# PowerCell-v13.net
KiCad netlist of a schematic drawn in EAGLE
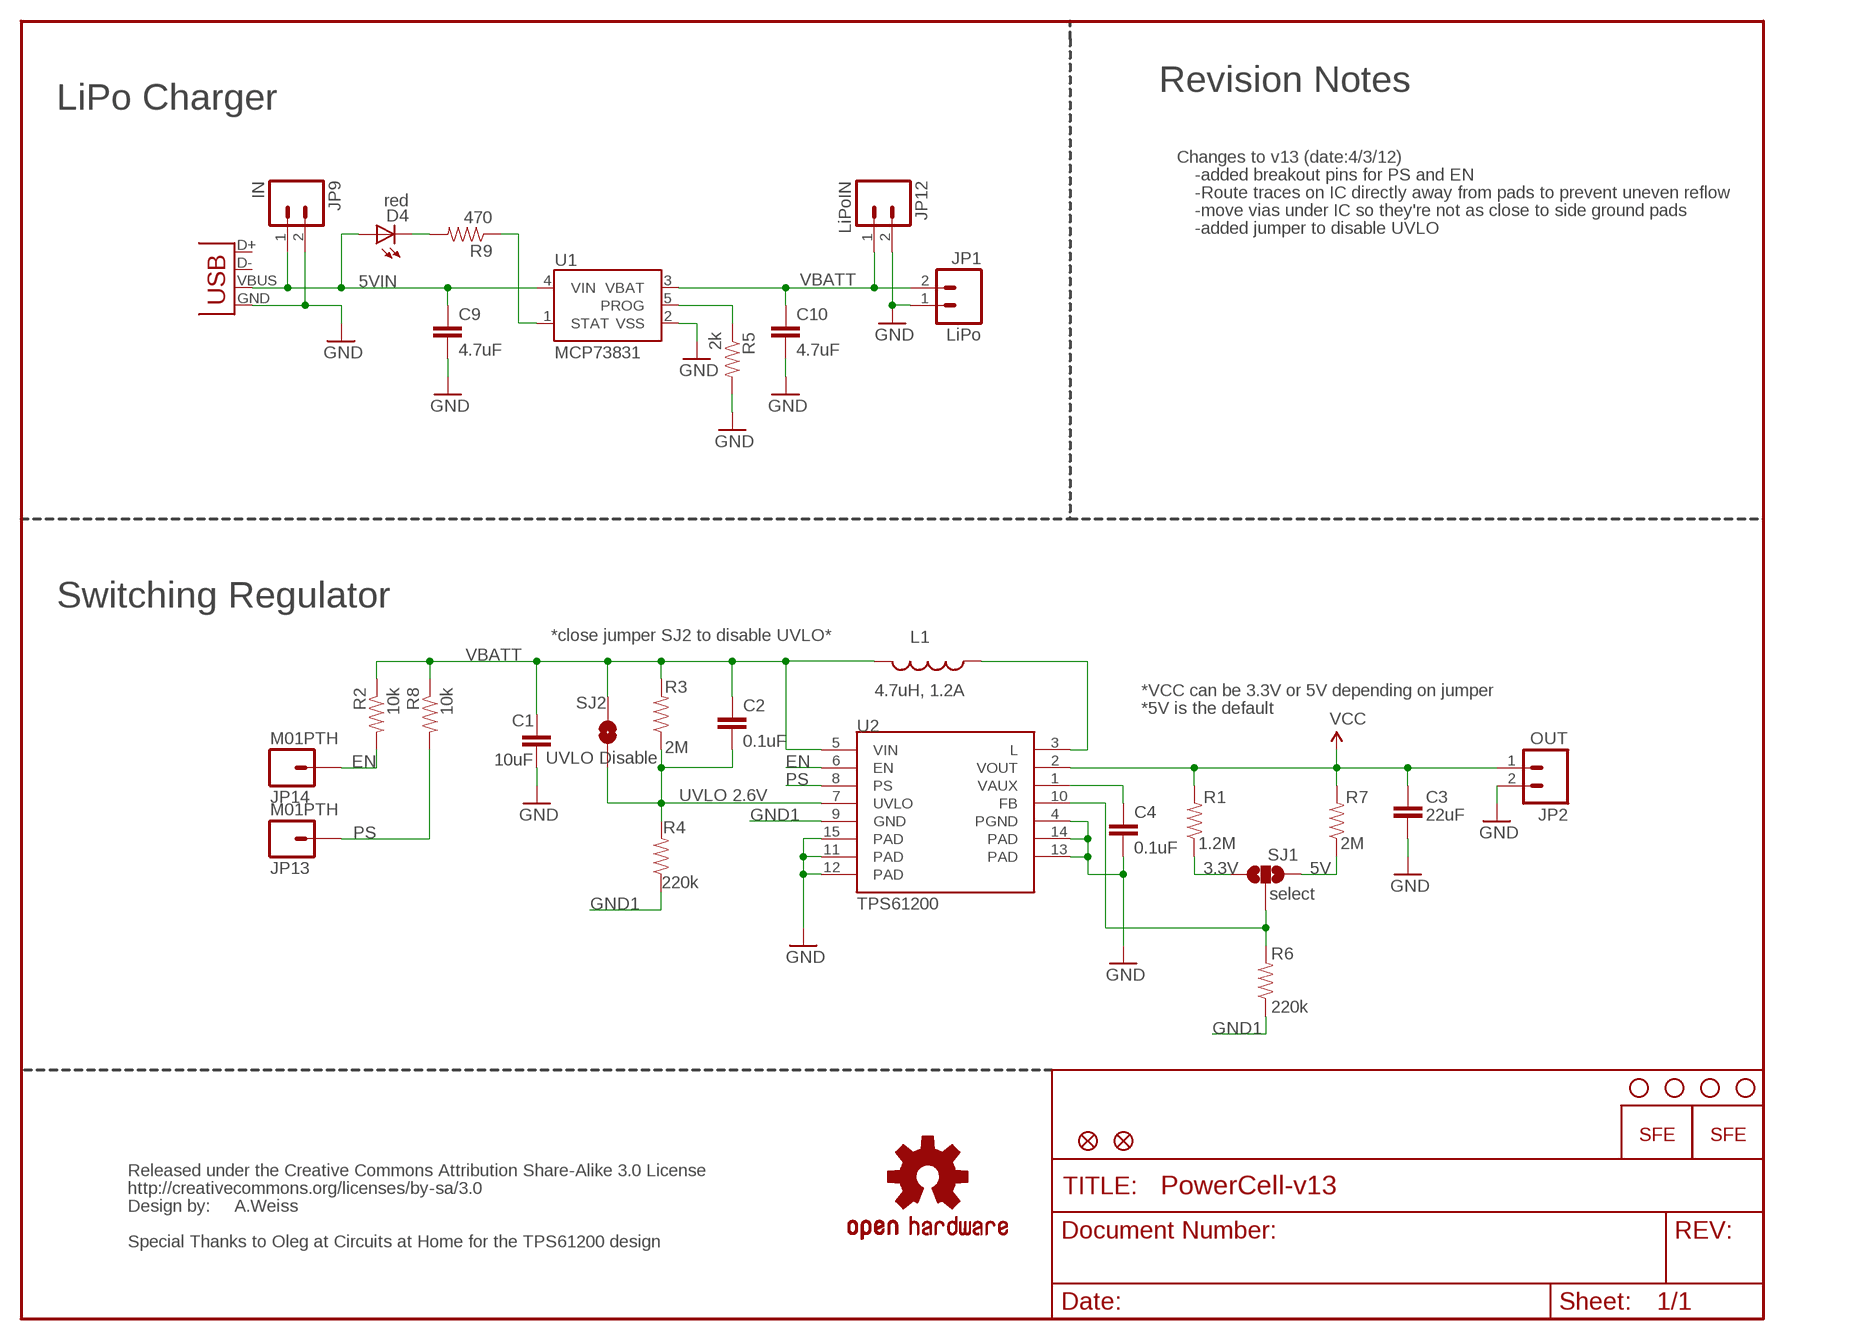
[diagram p0: schematic, sheet 1]

(export (version "E")
  (design (tool "Eeschema 10.0.6"))
  (components
    (comp (ref "C1")
      (value "10uF")
      (footprint "eagle-import:1206")
      (libsource (lib "eagle-import") (part "CAP1206"))
    )
    (comp (ref "C2")
      (value "0.1uF")
      (footprint "eagle-import:0402-CAP")
      (libsource (lib "eagle-import") (part "CAP0402-CAP"))
    )
    (comp (ref "C3")
      (value "22uF")
      (footprint "eagle-import:0805")
      (libsource (lib "eagle-import") (part "CAP0805"))
    )
    (comp (ref "C4")
      (value "0.1uF")
      (footprint "eagle-import:0402-CAP")
      (libsource (lib "eagle-import") (part "CAP0402-CAP"))
    )
    (comp (ref "C9")
      (value "4.7uF")
      (footprint "eagle-import:0402-CAP")
      (libsource (lib "eagle-import") (part "CAP0402-CAP"))
    )
    (comp (ref "C10")
      (value "4.7uF")
      (footprint "eagle-import:0402-CAP")
      (libsource (lib "eagle-import") (part "CAP0402-CAP"))
    )
    (comp (ref "D4")
      (value "red")
      (footprint "eagle-import:LED-0603")
      (libsource (lib "eagle-import") (part "LED0603"))
    )
    (comp (ref "JP1")
      (value "LiPo")
      (footprint "eagle-import:JST-2-SMD")
      (libsource (lib "eagle-import") (part "M02-JST-2MM-SMT"))
    )
    (comp (ref "JP2")
      (value "OUT")
      (footprint "eagle-import:1X02")
      (libsource (lib "eagle-import") (part "M02PTH"))
    )
    (comp (ref "JP3")
      (value "LOGO-SFENEW")
      (footprint "eagle-import:SFE-NEW-WEBLOGO")
      (libsource (lib "eagle-import") (part "LOGO-SFENEW"))
    )
    (comp (ref "JP4")
      (value "LOGO-SFESK")
      (footprint "eagle-import:SFE-LOGO-FLAME")
      (libsource (lib "eagle-import") (part "LOGO-SFESK"))
    )
    (comp (ref "JP5")
      (value "STAND-OFF")
      (footprint "eagle-import:STAND-OFF")
      (libsource (lib "eagle-import") (part "STAND-OFF"))
    )
    (comp (ref "JP6")
      (value "STAND-OFF")
      (footprint "eagle-import:STAND-OFF")
      (libsource (lib "eagle-import") (part "STAND-OFF"))
    )
    (comp (ref "JP7")
      (value "STAND-OFF")
      (footprint "eagle-import:STAND-OFF")
      (libsource (lib "eagle-import") (part "STAND-OFF"))
    )
    (comp (ref "JP8")
      (value "STAND-OFF")
      (footprint "eagle-import:STAND-OFF")
      (libsource (lib "eagle-import") (part "STAND-OFF"))
    )
    (comp (ref "JP9")
      (value "IN")
      (footprint "eagle-import:1X02")
      (libsource (lib "eagle-import") (part "M02PTH"))
    )
    (comp (ref "JP12")
      (value "LiPoIN")
      (footprint "eagle-import:1X02")
      (libsource (lib "eagle-import") (part "M02PTH"))
    )
    (comp (ref "JP13")
      (value "M01PTH")
      (footprint "eagle-import:1X01")
      (libsource (lib "eagle-import") (part "M01PTH"))
    )
    (comp (ref "JP14")
      (value "M01PTH")
      (footprint "eagle-import:1X01")
      (libsource (lib "eagle-import") (part "M01PTH"))
    )
    (comp (ref "JP15")
      (value "FIDUCIALUFIDUCIAL")
      (footprint "eagle-import:MICRO-FIDUCIAL")
      (libsource (lib "eagle-import") (part "FIDUCIALUFIDUCIAL"))
    )
    (comp (ref "JP16")
      (value "FIDUCIALUFIDUCIAL")
      (footprint "eagle-import:MICRO-FIDUCIAL")
      (libsource (lib "eagle-import") (part "FIDUCIALUFIDUCIAL"))
    )
    (comp (ref "L1")
      (value "4.7uH, 1.2A")
      (footprint "eagle-import:CDRH2D09")
      (libsource (lib "eagle-import") (part "INDUCTOR."))
    )
    (comp (ref "R1")
      (value "1.2M")
      (footprint "eagle-import:0402-RES")
      (libsource (lib "eagle-import") (part "RESISTOR0402-RES"))
    )
    (comp (ref "R2")
      (value "10k")
      (footprint "eagle-import:0402-RES")
      (libsource (lib "eagle-import") (part "RESISTOR0402-RES"))
    )
    (comp (ref "R3")
      (value "2M")
      (footprint "eagle-import:0402-RES")
      (libsource (lib "eagle-import") (part "RESISTOR0402-RES"))
    )
    (comp (ref "R4")
      (value "220k")
      (footprint "eagle-import:0402-RES")
      (libsource (lib "eagle-import") (part "RESISTOR0402-RES"))
    )
    (comp (ref "R5")
      (value "2k")
      (footprint "eagle-import:0402-RES")
      (libsource (lib "eagle-import") (part "RESISTOR0402-RES"))
    )
    (comp (ref "R6")
      (value "220k")
      (footprint "eagle-import:0402-RES")
      (libsource (lib "eagle-import") (part "RESISTOR0402-RES"))
    )
    (comp (ref "R7")
      (value "2M")
      (footprint "eagle-import:0402-RES")
      (libsource (lib "eagle-import") (part "RESISTOR0402-RES"))
    )
    (comp (ref "R8")
      (value "10k")
      (footprint "eagle-import:0402-RES")
      (libsource (lib "eagle-import") (part "RESISTOR0402-RES"))
    )
    (comp (ref "R9")
      (value "470")
      (footprint "eagle-import:0402-RES")
      (libsource (lib "eagle-import") (part "RESISTOR0402-RES"))
    )
    (comp (ref "SJ1")
      (value "select")
      (footprint "eagle-import:SJ_3_PASTE2&3")
      (libsource (lib "eagle-import") (part "SOLDERJUMPER_2WAYPASTE2&3"))
    )
    (comp (ref "SJ2")
      (value "UVLO Disable")
      (footprint "eagle-import:SJ_2S-NO")
      (libsource (lib "eagle-import") (part "SOLDERJUMPERNO"))
    )
    (comp (ref "U$1")
      (value "OSHW-LOGOS")
      (footprint "eagle-import:OSHW-LOGO-S")
      (libsource (lib "eagle-import") (part "OSHW-LOGOS"))
    )
    (comp (ref "U$2")
      (value "CREATIVE_COMMONS")
      (footprint "eagle-import:CREATIVE_COMMONS")
      (libsource (lib "eagle-import") (part "CREATIVE_COMMONS"))
    )
    (comp (ref "U1")
      (value "MCP73831")
      (footprint "eagle-import:SOT23-5")
      (libsource (lib "eagle-import") (part "MCP73831"))
    )
    (comp (ref "U2")
      (value "TPS61200")
      (footprint "eagle-import:QFN-10_PAD")
      (libsource (lib "eagle-import") (part "TPS61200"))
    )
    (comp (ref "X1")
      (value "USB-MICROB")
      (footprint "eagle-import:USB-MICROB")
      (libsource (lib "eagle-import") (part "USB-MICROB"))
    )
  )
  (nets
    (net (code "1") (name "/3.3V") (class "Default")
      (node (ref "R1") (pin "1") (pinfunction "1_1") (pintype "passive"))
      (node (ref "SJ1") (pin "1") (pinfunction "1_1") (pintype "passive"))
    )
    (net (code "2") (name "/5V") (class "Default")
      (node (ref "R7") (pin "1") (pinfunction "1_1") (pintype "passive"))
      (node (ref "SJ1") (pin "3") (pinfunction "3_3") (pintype "passive"))
    )
    (net (code "3") (name "/5VIN") (class "Default")
      (node (ref "C9") (pin "1") (pinfunction "1_1") (pintype "passive"))
      (node (ref "D4") (pin "A") (pinfunction "A_A") (pintype "passive"))
      (node (ref "JP9") (pin "1") (pinfunction "1_1") (pintype "passive"))
      (node (ref "U1") (pin "4") (pinfunction "VIN_4") (pintype "power_in"))
      (node (ref "X1") (pin "VBUS") (pinfunction "VBUS_VBUS") (pintype "bidirectional"))
    )
    (net (code "4") (name "/EN") (class "Default")
      (node (ref "JP14") (pin "1") (pinfunction "1_1") (pintype "passive"))
      (node (ref "R2") (pin "2") (pinfunction "2_2") (pintype "passive"))
      (node (ref "U2") (pin "6") (pinfunction "EN_6") (pintype "input"))
    )
    (net (code "5") (name "/GND1") (class "Default")
      (node (ref "R4") (pin "1") (pinfunction "1_1") (pintype "passive"))
      (node (ref "R6") (pin "1") (pinfunction "1_1") (pintype "passive"))
      (node (ref "U2") (pin "9") (pinfunction "GND_9") (pintype "power_in"))
    )
    (net (code "6") (name "/PS") (class "Default")
      (node (ref "JP13") (pin "1") (pinfunction "1_1") (pintype "passive"))
      (node (ref "R8") (pin "2") (pinfunction "2_2") (pintype "passive"))
      (node (ref "U2") (pin "8") (pinfunction "PS_8") (pintype "input"))
    )
    (net (code "7") (name "/VBATT") (class "Default")
      (node (ref "C1") (pin "1") (pinfunction "1_1") (pintype "passive"))
      (node (ref "C10") (pin "1") (pinfunction "1_1") (pintype "passive"))
      (node (ref "C2") (pin "1") (pinfunction "1_1") (pintype "passive"))
      (node (ref "JP1") (pin "2") (pinfunction "2_2") (pintype "passive"))
      (node (ref "JP12") (pin "1") (pinfunction "1_1") (pintype "passive"))
      (node (ref "L1") (pin "P$2") (pinfunction "2_P$2") (pintype "passive"))
      (node (ref "R2") (pin "1") (pinfunction "1_1") (pintype "passive"))
      (node (ref "R3") (pin "2") (pinfunction "2_2") (pintype "passive"))
      (node (ref "R8") (pin "1") (pinfunction "1_1") (pintype "passive"))
      (node (ref "SJ2") (pin "2") (pinfunction "2_2") (pintype "passive"))
      (node (ref "U1") (pin "3") (pinfunction "VBAT_3") (pintype "power_in"))
      (node (ref "U2") (pin "5") (pinfunction "VIN_5") (pintype "power_in"))
    )
    (net (code "8") (name "GND") (class "Default")
      (node (ref "C1") (pin "2") (pinfunction "2_2") (pintype "passive"))
      (node (ref "C10") (pin "2") (pinfunction "2_2") (pintype "passive"))
      (node (ref "C3") (pin "2") (pinfunction "2_2") (pintype "passive"))
      (node (ref "C4") (pin "2") (pinfunction "2_2") (pintype "passive"))
      (node (ref "C9") (pin "2") (pinfunction "2_2") (pintype "passive"))
      (node (ref "JP1") (pin "1") (pinfunction "1_1") (pintype "passive"))
      (node (ref "JP12") (pin "2") (pinfunction "2_2") (pintype "passive"))
      (node (ref "JP2") (pin "2") (pinfunction "2_2") (pintype "passive"))
      (node (ref "JP9") (pin "2") (pinfunction "2_2") (pintype "passive"))
      (node (ref "R5") (pin "2") (pinfunction "2_2") (pintype "passive"))
      (node (ref "U1") (pin "2") (pinfunction "VSS_2") (pintype "power_in"))
      (node (ref "U2") (pin "11") (pinfunction "PAD_11") (pintype "power_in"))
      (node (ref "U2") (pin "12") (pinfunction "PAD_12") (pintype "power_in"))
      (node (ref "U2") (pin "13") (pinfunction "PAD_13") (pintype "power_in"))
      (node (ref "U2") (pin "14") (pinfunction "PAD_14") (pintype "power_in"))
      (node (ref "U2") (pin "15") (pinfunction "PAD_15") (pintype "power_in"))
      (node (ref "U2") (pin "4") (pinfunction "PGND_4") (pintype "power_in"))
      (node (ref "X1") (pin "GND") (pinfunction "GND_GND") (pintype "bidirectional"))
    )
    (net (code "9") (name "Net-(D4-PadC)") (class "Default")
      (node (ref "D4") (pin "C") (pinfunction "C_C") (pintype "passive"))
      (node (ref "R9") (pin "2") (pinfunction "2_2") (pintype "passive"))
    )
    (net (code "10") (name "Net-(L1-1)") (class "Default")
      (node (ref "L1") (pin "P$1") (pinfunction "1_P$1") (pintype "passive"))
      (node (ref "U2") (pin "3") (pinfunction "L_3") (pintype "passive"))
    )
    (net (code "11") (name "Net-(U1-PROG)") (class "Default")
      (node (ref "R5") (pin "1") (pinfunction "1_1") (pintype "passive"))
      (node (ref "U1") (pin "5") (pinfunction "PROG_5") (pintype "input"))
    )
    (net (code "12") (name "Net-(U1-STAT)") (class "Default")
      (node (ref "R9") (pin "1") (pinfunction "1_1") (pintype "passive"))
      (node (ref "U1") (pin "1") (pinfunction "STAT_1") (pintype "output"))
    )
    (net (code "13") (name "Net-(U2-FB)") (class "Default")
      (node (ref "R6") (pin "2") (pinfunction "2_2") (pintype "passive"))
      (node (ref "SJ1") (pin "2") (pinfunction "2_2") (pintype "passive"))
      (node (ref "U2") (pin "10") (pinfunction "FB_10") (pintype "passive"))
    )
    (net (code "14") (name "Net-(U2-UVLO)") (class "Default")
      (node (ref "C2") (pin "2") (pinfunction "2_2") (pintype "passive"))
      (node (ref "R3") (pin "1") (pinfunction "1_1") (pintype "passive"))
      (node (ref "R4") (pin "2") (pinfunction "2_2") (pintype "passive"))
      (node (ref "SJ2") (pin "1") (pinfunction "1_1") (pintype "passive"))
      (node (ref "U2") (pin "7") (pinfunction "UVLO_7") (pintype "passive"))
    )
    (net (code "15") (name "Net-(U2-VAUX)") (class "Default")
      (node (ref "C4") (pin "1") (pinfunction "1_1") (pintype "passive"))
      (node (ref "U2") (pin "1") (pinfunction "VAUX_1") (pintype "passive"))
    )
    (net (code "16") (name "VCC") (class "Default")
      (node (ref "C3") (pin "1") (pinfunction "1_1") (pintype "passive"))
      (node (ref "JP2") (pin "1") (pinfunction "1_1") (pintype "passive"))
      (node (ref "R1") (pin "2") (pinfunction "2_2") (pintype "passive"))
      (node (ref "R7") (pin "2") (pinfunction "2_2") (pintype "passive"))
      (node (ref "U2") (pin "2") (pinfunction "VOUT_2") (pintype "passive"))
    )
    (net (code "17") (name "unconnected-(X1-PadD+)") (class "Default")
      (node (ref "X1") (pin "D+") (pinfunction "D+_D+") (pintype "bidirectional"))
    )
    (net (code "18") (name "unconnected-(X1-PadD-)") (class "Default")
      (node (ref "X1") (pin "D-") (pinfunction "D-_D-") (pintype "bidirectional"))
    )
  )
)
